# Buck_Driver_V2.net
KiCad netlist of a schematic drawn in EAGLE
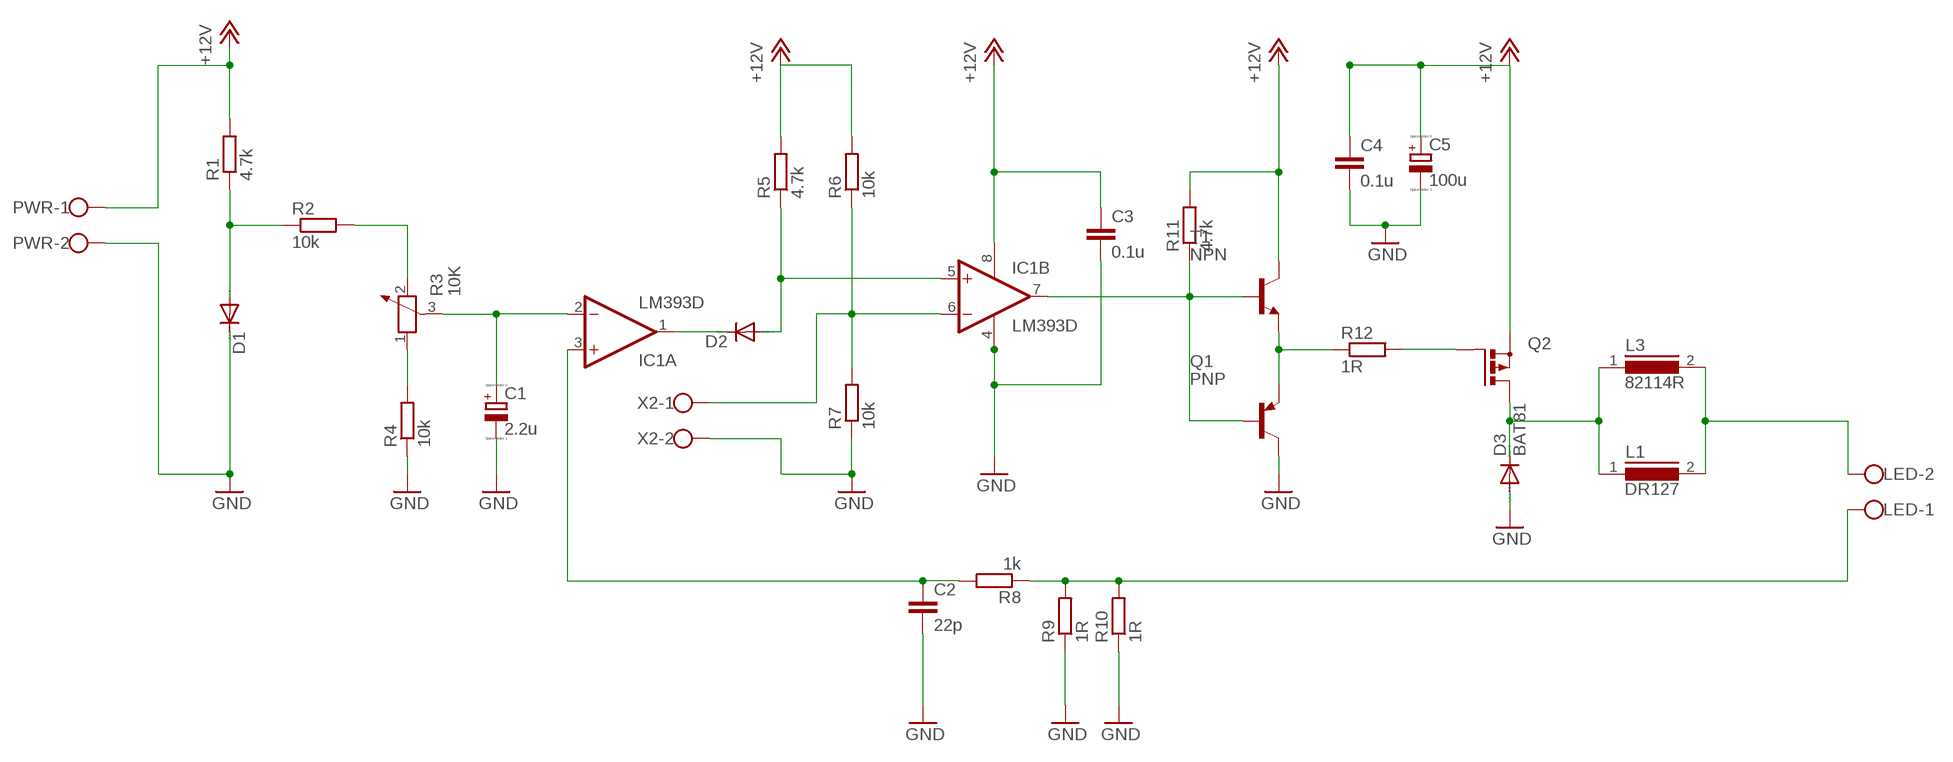
[diagram p0: schematic, sheet 1]

(export (version "E")
  (design (tool "Eeschema 10.0.6"))
  (components
    (comp (ref "C1")
      (value "2.2u")
      (footprint "eagle-import:140CLH-0810")
      (libsource (lib "eagle-import") (part "CPOL-EU140CLH-0810"))
    )
    (comp (ref "C2")
      (value "22p")
      (footprint "eagle-import:C1206")
      (libsource (lib "eagle-import") (part "C-EUC1206"))
    )
    (comp (ref "C3")
      (value "0.1u")
      (footprint "eagle-import:C1206")
      (libsource (lib "eagle-import") (part "C-EUC1206"))
    )
    (comp (ref "C4")
      (value "0.1u")
      (footprint "eagle-import:C1206")
      (libsource (lib "eagle-import") (part "C-EUC1206"))
    )
    (comp (ref "C5")
      (value "100u")
      (footprint "eagle-import:140CLH-0810")
      (libsource (lib "eagle-import") (part "CPOL-EU140CLH-0810"))
    )
    (comp (ref "D1")
      (value "DIODE-DO214BA")
      (footprint "eagle-import:DO214BA")
      (libsource (lib "eagle-import") (part "DIODE-DO214BA"))
    )
    (comp (ref "D2")
      (value "DIODE-DO214BA")
      (footprint "eagle-import:DO214BA")
      (libsource (lib "eagle-import") (part "DIODE-DO214BA"))
    )
    (comp (ref "D3")
      (value "BAT81")
      (footprint "eagle-import:DO34-7")
      (libsource (lib "eagle-import") (part "BAT81"))
    )
    (comp (ref "IC1")
      (value "LM393D")
      (footprint "eagle-import:SO08")
      (libsource (lib "eagle-import") (part "LM393D"))
    )
    (comp (ref "L1")
      (value "DR127")
      (footprint "eagle-import:DR127")
      (libsource (lib "eagle-import") (part "DR127"))
    )
    (comp (ref "L3")
      (value "82114R")
      (footprint "eagle-import:82114R")
      (libsource (lib "eagle-import") (part "82114R"))
    )
    (comp (ref "LED")
      (value "W237-102")
      (footprint "eagle-import:W237-102")
      (fields (field (name "MPN") "237-102"))
      (libsource (lib "eagle-import") (part "W237-102"))
    )
    (comp (ref "PWR")
      (value "W237-102")
      (footprint "eagle-import:W237-102")
      (fields (field (name "MPN") "237-102"))
      (libsource (lib "eagle-import") (part "W237-102"))
    )
    (comp (ref "Q1")
      (value "PNP")
      (footprint "eagle-import:SOT23-BEC")
      (libsource (lib "eagle-import") (part "BC856SMDALT1"))
    )
    (comp (ref "Q2")
      (value "PMOSFET_PTO220BH")
      (footprint "eagle-import:TO220BH")
      (libsource (lib "eagle-import") (part "PMOSFET_PTO220BH"))
    )
    (comp (ref "R1")
      (value "4.7k")
      (footprint "eagle-import:R1206")
      (libsource (lib "eagle-import") (part "R-EU_R1206"))
    )
    (comp (ref "R2")
      (value "10k")
      (footprint "eagle-import:R1206")
      (libsource (lib "eagle-import") (part "R-EU_R1206"))
    )
    (comp (ref "R3")
      (value "10K")
      (footprint "eagle-import:PT-SPIN")
      (libsource (lib "eagle-import") (part "POTENTIOMETER_PT_SPIN"))
    )
    (comp (ref "R4")
      (value "10k")
      (footprint "eagle-import:R1206")
      (libsource (lib "eagle-import") (part "R-EU_R1206"))
    )
    (comp (ref "R5")
      (value "4.7k")
      (footprint "eagle-import:R1206")
      (libsource (lib "eagle-import") (part "R-EU_R1206"))
    )
    (comp (ref "R6")
      (value "10k")
      (footprint "eagle-import:R1206")
      (libsource (lib "eagle-import") (part "R-EU_R1206"))
    )
    (comp (ref "R7")
      (value "10k")
      (footprint "eagle-import:R1206")
      (libsource (lib "eagle-import") (part "R-EU_R1206"))
    )
    (comp (ref "R8")
      (value "1k")
      (footprint "eagle-import:R1206")
      (libsource (lib "eagle-import") (part "R-EU_R1206"))
    )
    (comp (ref "R9")
      (value "1R")
      (footprint "eagle-import:R2512")
      (libsource (lib "eagle-import") (part "R-EU_R2512"))
    )
    (comp (ref "R10")
      (value "1R")
      (footprint "eagle-import:R2512")
      (libsource (lib "eagle-import") (part "R-EU_R2512"))
    )
    (comp (ref "R11")
      (value "4.7k")
      (footprint "eagle-import:R1206")
      (libsource (lib "eagle-import") (part "R-EU_R1206"))
    )
    (comp (ref "R12")
      (value "1R")
      (footprint "eagle-import:R1206")
      (libsource (lib "eagle-import") (part "R-EU_R1206"))
    )
    (comp (ref "T1")
      (value "NPN")
      (footprint "eagle-import:SOT23")
      (libsource (lib "eagle-import") (part "BC847"))
    )
    (comp (ref "X2")
      (value "W237-102")
      (footprint "eagle-import:W237-102")
      (fields (field (name "MPN") "237-102"))
      (libsource (lib "eagle-import") (part "W237-102"))
    )
  )
  (nets
    (net (code "1") (name "+12V") (class "Default")
      (node (ref "C3") (pin "1") (pinfunction "1_1") (pintype "passive"))
      (node (ref "C4") (pin "1") (pinfunction "1_1") (pintype "passive"))
      (node (ref "C5") (pin "+") (pinfunction "+_+") (pintype "passive"))
      (node (ref "IC1") (pin "8") (pinfunction "V+_8") (pintype "power_in"))
      (node (ref "PWR") (pin "1") (pinfunction "KL_1") (pintype "passive"))
      (node (ref "Q2") (pin "S") (pinfunction "S_S") (pintype "passive"))
      (node (ref "R1") (pin "2") (pinfunction "2_2") (pintype "passive"))
      (node (ref "R11") (pin "2") (pinfunction "2_2") (pintype "passive"))
      (node (ref "R5") (pin "2") (pinfunction "2_2") (pintype "passive"))
      (node (ref "R6") (pin "2") (pinfunction "2_2") (pintype "passive"))
      (node (ref "T1") (pin "3") (pinfunction "C_3") (pintype "passive"))
    )
    (net (code "2") (name "GND") (class "Default")
      (node (ref "C1") (pin "-") (pinfunction "-_-") (pintype "passive"))
      (node (ref "C2") (pin "2") (pinfunction "2_2") (pintype "passive"))
      (node (ref "C3") (pin "2") (pinfunction "2_2") (pintype "passive"))
      (node (ref "C4") (pin "2") (pinfunction "2_2") (pintype "passive"))
      (node (ref "C5") (pin "-") (pinfunction "-_-") (pintype "passive"))
      (node (ref "D1") (pin "C") (pinfunction "C_C") (pintype "passive"))
      (node (ref "D3") (pin "A") (pinfunction "A_A") (pintype "passive"))
      (node (ref "IC1") (pin "4") (pinfunction "V-_4") (pintype "power_in"))
      (node (ref "PWR") (pin "2") (pinfunction "KL_2") (pintype "passive"))
      (node (ref "Q1") (pin "C") (pinfunction "C_C") (pintype "passive"))
      (node (ref "R10") (pin "1") (pinfunction "1_1") (pintype "passive"))
      (node (ref "R4") (pin "1") (pinfunction "1_1") (pintype "passive"))
      (node (ref "R7") (pin "1") (pinfunction "1_1") (pintype "passive"))
      (node (ref "R9") (pin "1") (pinfunction "1_1") (pintype "passive"))
      (node (ref "X2") (pin "2") (pinfunction "KL_2") (pintype "passive"))
    )
    (net (code "3") (name "Net-(D1-PadA)") (class "Default")
      (node (ref "D1") (pin "A") (pinfunction "A_A") (pintype "passive"))
      (node (ref "R1") (pin "1") (pinfunction "1_1") (pintype "passive"))
      (node (ref "R2") (pin "1") (pinfunction "1_1") (pintype "passive"))
    )
    (net (code "4") (name "Net-(D3-PadC)") (class "Default")
      (node (ref "D3") (pin "C") (pinfunction "C_C") (pintype "passive"))
      (node (ref "L1") (pin "1") (pinfunction "1_1") (pintype "passive"))
      (node (ref "L3") (pin "1") (pinfunction "1_1") (pintype "passive"))
      (node (ref "Q2") (pin "D") (pinfunction "D_D") (pintype "passive"))
    )
    (net (code "5") (name "Net-(IC1A-+IN)") (class "Default")
      (node (ref "C2") (pin "1") (pinfunction "1_1") (pintype "passive"))
      (node (ref "IC1") (pin "3") (pinfunction "+IN_3") (pintype "input"))
      (node (ref "R8") (pin "2") (pinfunction "2_2") (pintype "passive"))
    )
    (net (code "6") (name "Net-(IC1A--IN)") (class "Default")
      (node (ref "C1") (pin "+") (pinfunction "+_+") (pintype "passive"))
      (node (ref "IC1") (pin "2") (pinfunction "-IN_2") (pintype "input"))
      (node (ref "R3") (pin "3") (pinfunction "3_3") (pintype "passive"))
    )
    (net (code "7") (name "Net-(IC1A-OUT)") (class "Default")
      (node (ref "D2") (pin "C") (pinfunction "C_C") (pintype "passive"))
      (node (ref "IC1") (pin "1") (pinfunction "OUT_1") (pintype "output"))
    )
    (net (code "8") (name "Net-(IC1B-+IN)") (class "Default")
      (node (ref "D2") (pin "A") (pinfunction "A_A") (pintype "passive"))
      (node (ref "IC1") (pin "5") (pinfunction "+IN_5") (pintype "input"))
      (node (ref "R5") (pin "1") (pinfunction "1_1") (pintype "passive"))
    )
    (net (code "9") (name "Net-(IC1B--IN)") (class "Default")
      (node (ref "IC1") (pin "6") (pinfunction "-IN_6") (pintype "input"))
      (node (ref "R6") (pin "1") (pinfunction "1_1") (pintype "passive"))
      (node (ref "R7") (pin "2") (pinfunction "2_2") (pintype "passive"))
      (node (ref "X2") (pin "1") (pinfunction "KL_1") (pintype "passive"))
    )
    (net (code "10") (name "Net-(IC1B-OUT)") (class "Default")
      (node (ref "IC1") (pin "7") (pinfunction "OUT_7") (pintype "output"))
      (node (ref "Q1") (pin "B") (pinfunction "B_B") (pintype "passive"))
      (node (ref "R11") (pin "1") (pinfunction "1_1") (pintype "passive"))
      (node (ref "T1") (pin "1") (pinfunction "B_1") (pintype "passive"))
    )
    (net (code "11") (name "Net-(LEDA-KL)") (class "Default")
      (node (ref "LED") (pin "1") (pinfunction "KL_1") (pintype "passive"))
      (node (ref "R10") (pin "2") (pinfunction "2_2") (pintype "passive"))
      (node (ref "R8") (pin "1") (pinfunction "1_1") (pintype "passive"))
      (node (ref "R9") (pin "2") (pinfunction "2_2") (pintype "passive"))
    )
    (net (code "12") (name "Net-(LEDB-KL)") (class "Default")
      (node (ref "L1") (pin "2") (pinfunction "2_2") (pintype "passive"))
      (node (ref "L3") (pin "2") (pinfunction "2_2") (pintype "passive"))
      (node (ref "LED") (pin "2") (pinfunction "KL_2") (pintype "passive"))
    )
    (net (code "13") (name "Net-(Q2-PadG)") (class "Default")
      (node (ref "Q2") (pin "G") (pinfunction "G_G") (pintype "passive"))
      (node (ref "R12") (pin "2") (pinfunction "2_2") (pintype "passive"))
    )
    (net (code "14") (name "Net-(R2-Pad2)") (class "Default")
      (node (ref "R2") (pin "2") (pinfunction "2_2") (pintype "passive"))
      (node (ref "R3") (pin "2") (pinfunction "2_2") (pintype "passive"))
    )
    (net (code "15") (name "Net-(R3-Pad1)") (class "Default")
      (node (ref "R3") (pin "1") (pinfunction "1_1") (pintype "passive"))
      (node (ref "R4") (pin "2") (pinfunction "2_2") (pintype "passive"))
    )
    (net (code "16") (name "Net-(T1-E)") (class "Default")
      (node (ref "Q1") (pin "E") (pinfunction "E_E") (pintype "passive"))
      (node (ref "R12") (pin "1") (pinfunction "1_1") (pintype "passive"))
      (node (ref "T1") (pin "2") (pinfunction "E_2") (pintype "passive"))
    )
  )
)
